# RS485.net
KiCad netlist of a schematic drawn in Altium Designer
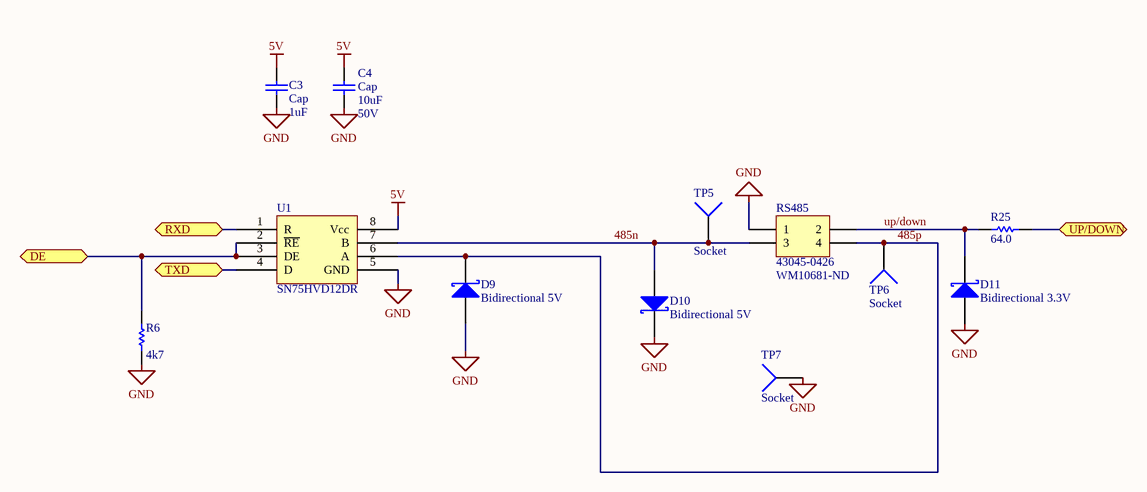
[diagram p0: RS485.SchDoc]

(export (version "E")
  (design (tool "Eeschema 10.0.6"))
  (components
    (comp (ref "C3")
      (value "Cap")
      (footprint "RESC3116X65N")
      (description "Capacitor")
      (fields
        (field (name "ALTIUM_VALUE") "1uF")
        (field (name "MANUFACTURER PART NUMBER") "CL31B105KCHNNNE")
        (field (name "VENDOR PART NUMBER") "1276-1838-1-ND")
      )
      (libsource (lib "Miscellaneous Devices") (part "Cap"))
    )
    (comp (ref "C4")
      (value "Cap")
      (footprint "CAPC3216X180N")
      (description "Capacitor")
      (fields
        (field (name "ALTIUM_VALUE") "10uF")
        (field (name "MANUFACTURER PART NUMBER") "CL31A106MBHNNNE")
        (field (name "VENDOR PART NUMBER") "1276-6736-1-ND")
        (field (name "VOLTAGE RATING") "50V")
      )
      (libsource (lib "Miscellaneous Devices") (part "Cap"))
    )
    (comp (ref "D9")
      (value "Bidirectional 5V")
      (footprint "THRMC0603X33N")
      (description "TVS")
      (fields
        (field (name "MANUFACTURER PART NUMBER") "CPDUC5V0R-HF")
        (field (name "VENDOR PART NUMBER") "641-1764-1-ND")
      )
      (libsource (lib "Miscellaneous Devices") (part "Diode 10TQ040"))
    )
    (comp (ref "D10")
      (value "Bidirectional 5V")
      (footprint "THRMC0603X33N")
      (description "TVS")
      (fields
        (field (name "MANUFACTURER PART NUMBER") "CPDUC5V0R-HF")
        (field (name "VENDOR PART NUMBER") "641-1764-1-ND")
      )
      (libsource (lib "Miscellaneous Devices") (part "Diode 10TQ040"))
    )
    (comp (ref "D11")
      (value "Bidirectional 3.3V")
      (footprint "THRMC0603X33N")
      (description "TVS")
      (fields
        (field (name "MANUFACTURER PART NUMBER") "SP1103C-01UTG")
        (field (name "VENDOR PART NUMBER") "F10154CT-ND")
      )
      (libsource (lib "Miscellaneous Devices") (part "Diode 10TQ040"))
    )
    (comp (ref "R6")
      (value "4k7")
      (footprint "0402")
      (description "Resistor")
      (fields
        (field (name "MANUFACTURER PART NUMBER") "RC0402FR-074K7L")
        (field (name "VENDOR PART NUMBER") "311-4.7KLRCT-ND")
      )
      (libsource (lib "Miscellaneous Devices") (part "Res1"))
    )
    (comp (ref "R25")
      (value "64.0")
      (footprint "0402")
      (description "Resistor")
      (fields
        (field (name "MANUFACTURER PART NUMBER") "RC0402FR-0760R4L")
        (field (name "VENDOR PART NUMBER") "311-60.4LRCT-ND")
      )
      (libsource (lib "Miscellaneous Devices") (part "Res1"))
    )
    (comp (ref "RS485")
      (value "43045-0426")
      (footprint "43045-0426")
      (description "Header, 2-Pin, Dual row")
      (fields (field (name "VENDOR PART NUMBER") "WM10681-ND") (field (name "PUBLISHER") "Altium Limited"))
      (libsource (lib "Miscellaneous Connectors") (part "Header 2X2"))
    )
    (comp (ref "TP5")
      (value "Socket")
      (footprint "5006")
      (fields
        (field (name "MANUFACTURER PART NUMBER") "5006")
        (field (name "VENDOR PART NUMBER") "36-5006-ND")
        (field (name "PUBLISHER") "Altium Limited")
      )
      (libsource (lib "Miscellaneous Connectors") (part "Socket"))
    )
    (comp (ref "TP6")
      (value "Socket")
      (footprint "5006")
      (fields
        (field (name "MANUFACTURER PART NUMBER") "5006")
        (field (name "VENDOR PART NUMBER") "36-5006-ND")
        (field (name "PUBLISHER") "Altium Limited")
      )
      (libsource (lib "Miscellaneous Connectors") (part "Socket"))
    )
    (comp (ref "TP7")
      (value "Socket")
      (footprint "5006")
      (fields
        (field (name "MANUFACTURER PART NUMBER") "5006")
        (field (name "VENDOR PART NUMBER") "36-5006-ND")
        (field (name "PUBLISHER") "Altium Limited")
      )
      (libsource (lib "Miscellaneous Connectors") (part "Socket"))
    )
    (comp (ref "U1")
      (value "SN75HVD12DR")
      (footprint "SOIC127P599X175-8N")
      (fields
        (field (name "MANUFACTURER PART NUMBER") "THVD1450DR")
        (field (name "VENDOR PART NUMBER") "296-50395-1-ND")
      )
      (libsource (lib "BeagleCape") (part "SN75HVD12DR"))
    )
  )
  (nets
    (net (code "1") (name "/485n") (class "Default")
      (node (ref "D10") (pin "3") (pinfunction "A_3") (pintype "passive"))
      (node (ref "RS485") (pin "3") (pinfunction "3_3") (pintype "passive"))
      (node (ref "TP5") (pin "1") (pinfunction "1_1") (pintype "passive"))
      (node (ref "U1") (pin "7") (pinfunction "B_7") (pintype "passive"))
    )
    (net (code "2") (name "/485p") (class "Default")
      (node (ref "D9") (pin "1") (pinfunction "K_1") (pintype "passive"))
      (node (ref "RS485") (pin "4") (pinfunction "4_4") (pintype "passive"))
      (node (ref "TP6") (pin "1") (pinfunction "1_1") (pintype "passive"))
      (node (ref "U1") (pin "6") (pinfunction "A_6") (pintype "passive"))
    )
    (net (code "3") (name "/DE") (class "Default")
      (node (ref "R6") (pin "1") (pinfunction "1_1") (pintype "passive"))
      (node (ref "U1") (pin "2") (pinfunction "~{RE}_2") (pintype "passive"))
      (node (ref "U1") (pin "3") (pinfunction "DE_3") (pintype "passive"))
    )
    (net (code "4") (name "/RXD") (class "Default")
      (node (ref "U1") (pin "1") (pinfunction "R_1") (pintype "passive"))
    )
    (net (code "5") (name "/TXD") (class "Default")
      (node (ref "U1") (pin "4") (pinfunction "D_4") (pintype "passive"))
    )
    (net (code "6") (name "/UP{slash}DOWN") (class "Default")
      (node (ref "R25") (pin "1") (pinfunction "1_1") (pintype "passive"))
    )
    (net (code "7") (name "/up{slash}down") (class "Default")
      (node (ref "D11") (pin "1") (pinfunction "K_1") (pintype "passive"))
      (node (ref "R25") (pin "2") (pinfunction "2_2") (pintype "passive"))
      (node (ref "RS485") (pin "2") (pinfunction "2_2") (pintype "passive"))
    )
    (net (code "8") (name "5V") (class "Default")
      (node (ref "C3") (pin "2") (pinfunction "2_2") (pintype "passive"))
      (node (ref "C4") (pin "2") (pinfunction "2_2") (pintype "passive"))
      (node (ref "U1") (pin "8") (pinfunction "Vcc_8") (pintype "passive"))
    )
    (net (code "9") (name "GND") (class "Default")
      (node (ref "C3") (pin "1") (pinfunction "1_1") (pintype "passive"))
      (node (ref "C4") (pin "1") (pinfunction "1_1") (pintype "passive"))
      (node (ref "D10") (pin "1") (pinfunction "K_1") (pintype "passive"))
      (node (ref "D11") (pin "3") (pinfunction "A_3") (pintype "passive"))
      (node (ref "D9") (pin "3") (pinfunction "A_3") (pintype "passive"))
      (node (ref "R6") (pin "2") (pinfunction "2_2") (pintype "passive"))
      (node (ref "RS485") (pin "1") (pinfunction "1_1") (pintype "passive"))
      (node (ref "TP7") (pin "1") (pinfunction "1_1") (pintype "passive"))
      (node (ref "U1") (pin "5") (pinfunction "GND_5") (pintype "passive"))
    )
  )
)
